# h-Remote.net
KiCad netlist of a schematic drawn in EAGLE
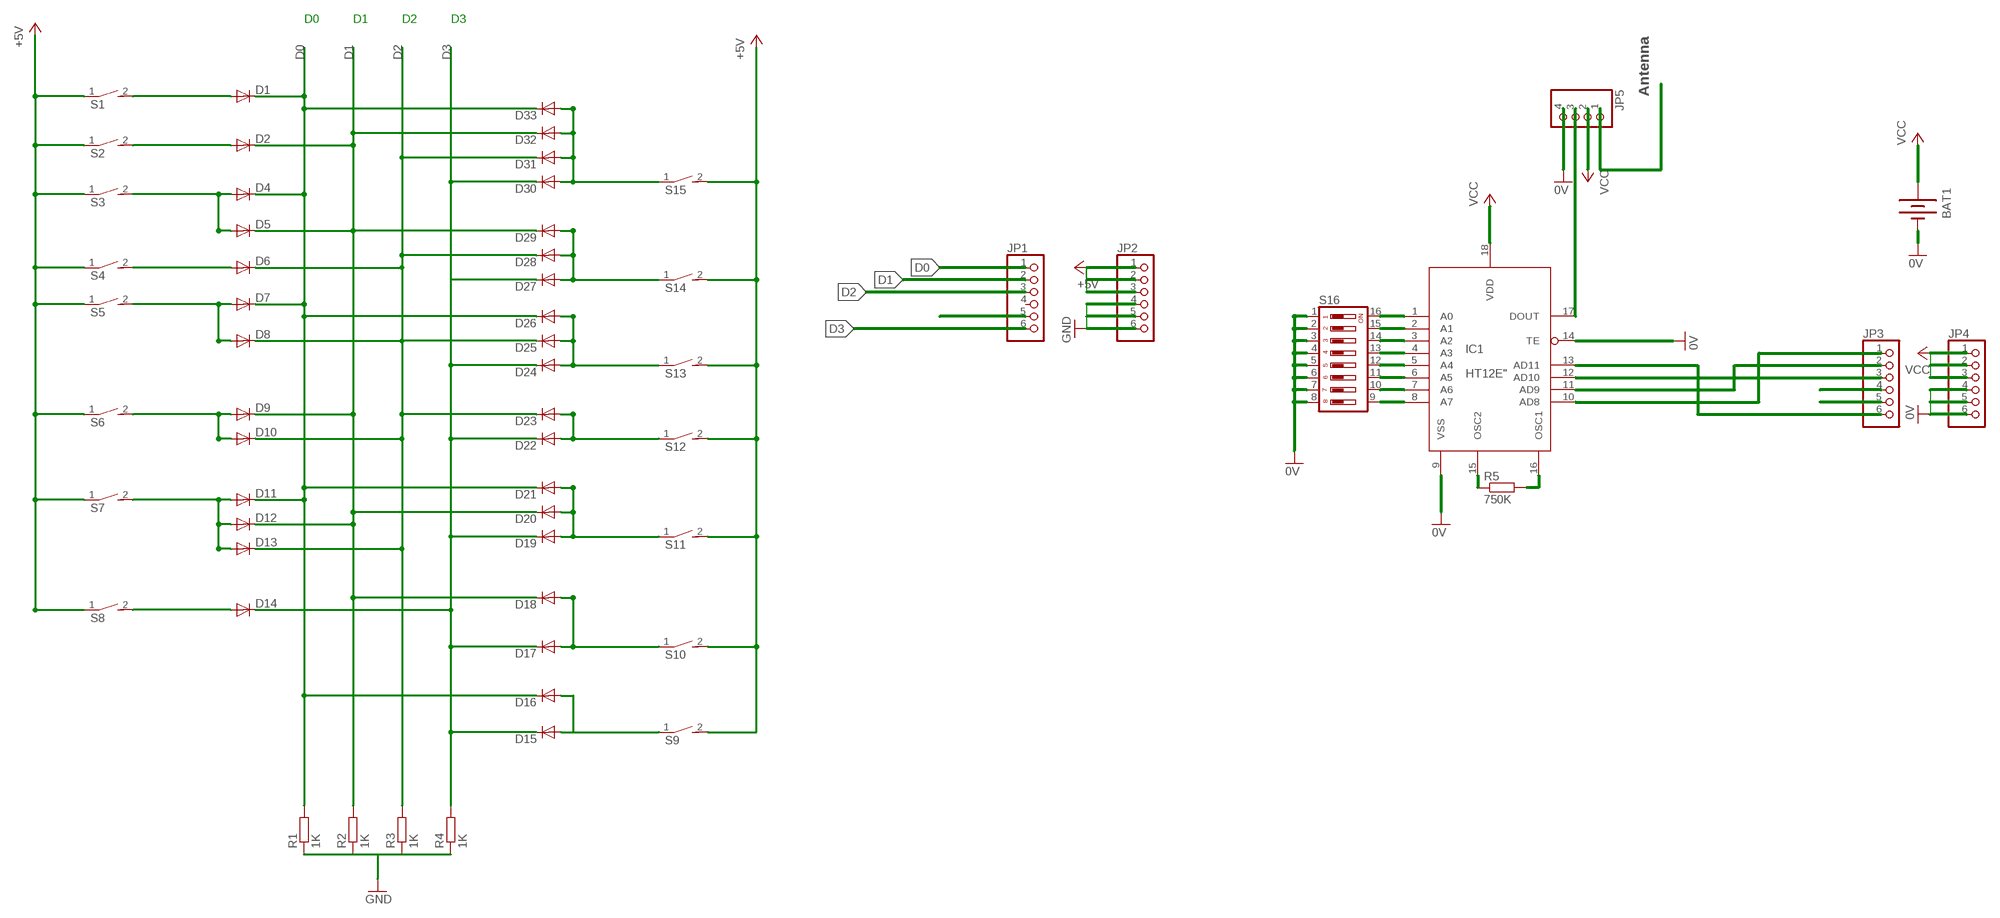
[diagram p0: schematic, sheet 1]

(export (version "E")
  (design (tool "Eeschema 10.0.6"))
  (components
    (comp (ref "BAT1")
      (value "BATTERY20PTH")
      (footprint "eagle-import:BATTCOM_20MM_PTH")
      (libsource (lib "eagle-import") (part "BATTERY20PTH"))
    )
    (comp (ref "D1")
      (value "DIODE-MELF-MLL41")
      (footprint "eagle-import:MELF-MLL41")
      (libsource (lib "eagle-import") (part "DIODE-MELF-MLL41"))
    )
    (comp (ref "D2")
      (value "DIODE-MELF-MLL41")
      (footprint "eagle-import:MELF-MLL41")
      (libsource (lib "eagle-import") (part "DIODE-MELF-MLL41"))
    )
    (comp (ref "D4")
      (value "DIODE-MELF-MLL41")
      (footprint "eagle-import:MELF-MLL41")
      (libsource (lib "eagle-import") (part "DIODE-MELF-MLL41"))
    )
    (comp (ref "D5")
      (value "DIODE-MELF-MLL41")
      (footprint "eagle-import:MELF-MLL41")
      (libsource (lib "eagle-import") (part "DIODE-MELF-MLL41"))
    )
    (comp (ref "D6")
      (value "DIODE-MELF-MLL41")
      (footprint "eagle-import:MELF-MLL41")
      (libsource (lib "eagle-import") (part "DIODE-MELF-MLL41"))
    )
    (comp (ref "D7")
      (value "DIODE-MELF-MLL41")
      (footprint "eagle-import:MELF-MLL41")
      (libsource (lib "eagle-import") (part "DIODE-MELF-MLL41"))
    )
    (comp (ref "D8")
      (value "DIODE-MELF-MLL41")
      (footprint "eagle-import:MELF-MLL41")
      (libsource (lib "eagle-import") (part "DIODE-MELF-MLL41"))
    )
    (comp (ref "D9")
      (value "DIODE-MELF-MLL41")
      (footprint "eagle-import:MELF-MLL41")
      (libsource (lib "eagle-import") (part "DIODE-MELF-MLL41"))
    )
    (comp (ref "D10")
      (value "DIODE-MELF-MLL41")
      (footprint "eagle-import:MELF-MLL41")
      (libsource (lib "eagle-import") (part "DIODE-MELF-MLL41"))
    )
    (comp (ref "D11")
      (value "DIODE-MELF-MLL41")
      (footprint "eagle-import:MELF-MLL41")
      (libsource (lib "eagle-import") (part "DIODE-MELF-MLL41"))
    )
    (comp (ref "D12")
      (value "DIODE-MELF-MLL41")
      (footprint "eagle-import:MELF-MLL41")
      (libsource (lib "eagle-import") (part "DIODE-MELF-MLL41"))
    )
    (comp (ref "D13")
      (value "DIODE-MELF-MLL41")
      (footprint "eagle-import:MELF-MLL41")
      (libsource (lib "eagle-import") (part "DIODE-MELF-MLL41"))
    )
    (comp (ref "D14")
      (value "DIODE-MELF-MLL41")
      (footprint "eagle-import:MELF-MLL41")
      (libsource (lib "eagle-import") (part "DIODE-MELF-MLL41"))
    )
    (comp (ref "D15")
      (value "DIODE-MELF-MLL41")
      (footprint "eagle-import:MELF-MLL41")
      (libsource (lib "eagle-import") (part "DIODE-MELF-MLL41"))
    )
    (comp (ref "D16")
      (value "DIODE-MELF-MLL41")
      (footprint "eagle-import:MELF-MLL41")
      (libsource (lib "eagle-import") (part "DIODE-MELF-MLL41"))
    )
    (comp (ref "D17")
      (value "DIODE-MELF-MLL41")
      (footprint "eagle-import:MELF-MLL41")
      (libsource (lib "eagle-import") (part "DIODE-MELF-MLL41"))
    )
    (comp (ref "D18")
      (value "DIODE-MELF-MLL41")
      (footprint "eagle-import:MELF-MLL41")
      (libsource (lib "eagle-import") (part "DIODE-MELF-MLL41"))
    )
    (comp (ref "D19")
      (value "DIODE-MELF-MLL41")
      (footprint "eagle-import:MELF-MLL41")
      (libsource (lib "eagle-import") (part "DIODE-MELF-MLL41"))
    )
    (comp (ref "D20")
      (value "DIODE-MELF-MLL41")
      (footprint "eagle-import:MELF-MLL41")
      (libsource (lib "eagle-import") (part "DIODE-MELF-MLL41"))
    )
    (comp (ref "D21")
      (value "DIODE-MELF-MLL41")
      (footprint "eagle-import:MELF-MLL41")
      (libsource (lib "eagle-import") (part "DIODE-MELF-MLL41"))
    )
    (comp (ref "D22")
      (value "DIODE-MELF-MLL41")
      (footprint "eagle-import:MELF-MLL41")
      (libsource (lib "eagle-import") (part "DIODE-MELF-MLL41"))
    )
    (comp (ref "D23")
      (value "DIODE-MELF-MLL41")
      (footprint "eagle-import:MELF-MLL41")
      (libsource (lib "eagle-import") (part "DIODE-MELF-MLL41"))
    )
    (comp (ref "D24")
      (value "DIODE-MELF-MLL41")
      (footprint "eagle-import:MELF-MLL41")
      (libsource (lib "eagle-import") (part "DIODE-MELF-MLL41"))
    )
    (comp (ref "D25")
      (value "DIODE-MELF-MLL41")
      (footprint "eagle-import:MELF-MLL41")
      (libsource (lib "eagle-import") (part "DIODE-MELF-MLL41"))
    )
    (comp (ref "D26")
      (value "DIODE-MELF-MLL41")
      (footprint "eagle-import:MELF-MLL41")
      (libsource (lib "eagle-import") (part "DIODE-MELF-MLL41"))
    )
    (comp (ref "D27")
      (value "DIODE-MELF-MLL41")
      (footprint "eagle-import:MELF-MLL41")
      (libsource (lib "eagle-import") (part "DIODE-MELF-MLL41"))
    )
    (comp (ref "D28")
      (value "DIODE-MELF-MLL41")
      (footprint "eagle-import:MELF-MLL41")
      (libsource (lib "eagle-import") (part "DIODE-MELF-MLL41"))
    )
    (comp (ref "D29")
      (value "DIODE-MELF-MLL41")
      (footprint "eagle-import:MELF-MLL41")
      (libsource (lib "eagle-import") (part "DIODE-MELF-MLL41"))
    )
    (comp (ref "D30")
      (value "DIODE-MELF-MLL41")
      (footprint "eagle-import:MELF-MLL41")
      (libsource (lib "eagle-import") (part "DIODE-MELF-MLL41"))
    )
    (comp (ref "D31")
      (value "DIODE-MELF-MLL41")
      (footprint "eagle-import:MELF-MLL41")
      (libsource (lib "eagle-import") (part "DIODE-MELF-MLL41"))
    )
    (comp (ref "D32")
      (value "DIODE-MELF-MLL41")
      (footprint "eagle-import:MELF-MLL41")
      (libsource (lib "eagle-import") (part "DIODE-MELF-MLL41"))
    )
    (comp (ref "D33")
      (value "DIODE-MELF-MLL41")
      (footprint "eagle-import:MELF-MLL41")
      (libsource (lib "eagle-import") (part "DIODE-MELF-MLL41"))
    )
    (comp (ref "IC1")
      (value "HT12E\"")
      (footprint "eagle-import:18-DIP-A")
      (libsource (lib "eagle-import") (part "HT12E{dblquote}"))
    )
    (comp (ref "JP1")
      (value "PINHD-1X6")
      (footprint "eagle-import:1X06")
      (libsource (lib "eagle-import") (part "PINHD-1X6"))
    )
    (comp (ref "JP2")
      (value "PINHD-1X6")
      (footprint "eagle-import:1X06")
      (libsource (lib "eagle-import") (part "PINHD-1X6"))
    )
    (comp (ref "JP3")
      (value "PINHD-1X6")
      (footprint "eagle-import:1X06")
      (libsource (lib "eagle-import") (part "PINHD-1X6"))
    )
    (comp (ref "JP4")
      (value "PINHD-1X6")
      (footprint "eagle-import:1X06")
      (libsource (lib "eagle-import") (part "PINHD-1X6"))
    )
    (comp (ref "JP5")
      (value "PINHD-1X4")
      (footprint "eagle-import:1X04")
      (libsource (lib "eagle-import") (part "PINHD-1X4"))
    )
    (comp (ref "R1")
      (value "1K")
      (footprint "eagle-import:R1206")
      (libsource (lib "eagle-import") (part "R-EU_R1206"))
    )
    (comp (ref "R2")
      (value "1K")
      (footprint "eagle-import:R1206")
      (libsource (lib "eagle-import") (part "R-EU_R1206"))
    )
    (comp (ref "R3")
      (value "1K")
      (footprint "eagle-import:R1206")
      (libsource (lib "eagle-import") (part "R-EU_R1206"))
    )
    (comp (ref "R4")
      (value "1K")
      (footprint "eagle-import:R1206")
      (libsource (lib "eagle-import") (part "R-EU_R1206"))
    )
    (comp (ref "R5")
      (value "750K")
      (footprint "eagle-import:0207_10")
      (libsource (lib "eagle-import") (part "R-EU_0207/10"))
    )
    (comp (ref "S1")
      (value "DS01E")
      (footprint "eagle-import:DS-01")
      (libsource (lib "eagle-import") (part "DS01E"))
    )
    (comp (ref "S2")
      (value "DS01E")
      (footprint "eagle-import:DS-01")
      (libsource (lib "eagle-import") (part "DS01E"))
    )
    (comp (ref "S3")
      (value "DS01E")
      (footprint "eagle-import:DS-01")
      (libsource (lib "eagle-import") (part "DS01E"))
    )
    (comp (ref "S4")
      (value "DS01E")
      (footprint "eagle-import:DS-01")
      (libsource (lib "eagle-import") (part "DS01E"))
    )
    (comp (ref "S5")
      (value "DS01E")
      (footprint "eagle-import:DS-01")
      (libsource (lib "eagle-import") (part "DS01E"))
    )
    (comp (ref "S6")
      (value "DS01E")
      (footprint "eagle-import:DS-01")
      (libsource (lib "eagle-import") (part "DS01E"))
    )
    (comp (ref "S7")
      (value "DS01E")
      (footprint "eagle-import:DS-01")
      (libsource (lib "eagle-import") (part "DS01E"))
    )
    (comp (ref "S8")
      (value "DS01E")
      (footprint "eagle-import:DS-01")
      (libsource (lib "eagle-import") (part "DS01E"))
    )
    (comp (ref "S9")
      (value "DS01E")
      (footprint "eagle-import:DS-01")
      (libsource (lib "eagle-import") (part "DS01E"))
    )
    (comp (ref "S10")
      (value "DS01E")
      (footprint "eagle-import:DS-01")
      (libsource (lib "eagle-import") (part "DS01E"))
    )
    (comp (ref "S11")
      (value "DS01E")
      (footprint "eagle-import:DS-01")
      (libsource (lib "eagle-import") (part "DS01E"))
    )
    (comp (ref "S12")
      (value "DS01E")
      (footprint "eagle-import:DS-01")
      (libsource (lib "eagle-import") (part "DS01E"))
    )
    (comp (ref "S13")
      (value "DS01E")
      (footprint "eagle-import:DS-01")
      (libsource (lib "eagle-import") (part "DS01E"))
    )
    (comp (ref "S14")
      (value "DS01E")
      (footprint "eagle-import:DS-01")
      (libsource (lib "eagle-import") (part "DS01E"))
    )
    (comp (ref "S15")
      (value "DS01E")
      (footprint "eagle-import:DS-01")
      (libsource (lib "eagle-import") (part "DS01E"))
    )
    (comp (ref "S16")
      (value "DIP08YL")
      (footprint "eagle-import:DIP08YL")
      (libsource (lib "eagle-import") (part "DIP08YL"))
    )
  )
  (nets
    (net (code "1") (name "+5V") (class "Default")
      (node (ref "JP2") (pin "1") (pinfunction "1_1") (pintype "passive"))
      (node (ref "JP2") (pin "2") (pinfunction "2_2") (pintype "passive"))
      (node (ref "JP2") (pin "3") (pinfunction "3_3") (pintype "passive"))
      (node (ref "S1") (pin "1") (pinfunction "1_1") (pintype "passive"))
      (node (ref "S10") (pin "2") (pinfunction "2_2") (pintype "passive"))
      (node (ref "S11") (pin "2") (pinfunction "2_2") (pintype "passive"))
      (node (ref "S12") (pin "2") (pinfunction "2_2") (pintype "passive"))
      (node (ref "S13") (pin "2") (pinfunction "2_2") (pintype "passive"))
      (node (ref "S14") (pin "2") (pinfunction "2_2") (pintype "passive"))
      (node (ref "S15") (pin "2") (pinfunction "2_2") (pintype "passive"))
      (node (ref "S2") (pin "1") (pinfunction "1_1") (pintype "passive"))
      (node (ref "S3") (pin "1") (pinfunction "1_1") (pintype "passive"))
      (node (ref "S4") (pin "1") (pinfunction "1_1") (pintype "passive"))
      (node (ref "S5") (pin "1") (pinfunction "1_1") (pintype "passive"))
      (node (ref "S6") (pin "1") (pinfunction "1_1") (pintype "passive"))
      (node (ref "S7") (pin "1") (pinfunction "1_1") (pintype "passive"))
      (node (ref "S8") (pin "1") (pinfunction "1_1") (pintype "passive"))
      (node (ref "S9") (pin "2") (pinfunction "2_2") (pintype "passive"))
    )
    (net (code "2") (name "0V") (class "Default")
      (node (ref "BAT1") (pin "2") (pinfunction "-_2") (pintype "power_in"))
      (node (ref "IC1") (pin "14") (pinfunction "TE_14") (pintype "power_in"))
      (node (ref "IC1") (pin "9") (pinfunction "VSS_9") (pintype "power_in"))
      (node (ref "JP4") (pin "4") (pinfunction "4_4") (pintype "passive"))
      (node (ref "JP4") (pin "5") (pinfunction "5_5") (pintype "passive"))
      (node (ref "JP4") (pin "6") (pinfunction "6_6") (pintype "passive"))
      (node (ref "JP5") (pin "4") (pinfunction "4_4") (pintype "passive"))
      (node (ref "S16") (pin "1") (pinfunction "1_1") (pintype "passive"))
      (node (ref "S16") (pin "2") (pinfunction "2_2") (pintype "passive"))
      (node (ref "S16") (pin "3") (pinfunction "3_3") (pintype "passive"))
      (node (ref "S16") (pin "4") (pinfunction "4_4") (pintype "passive"))
      (node (ref "S16") (pin "5") (pinfunction "5_5") (pintype "passive"))
      (node (ref "S16") (pin "6") (pinfunction "6_6") (pintype "passive"))
      (node (ref "S16") (pin "7") (pinfunction "7_7") (pintype "passive"))
      (node (ref "S16") (pin "8") (pinfunction "8_8") (pintype "passive"))
    )
    (net (code "3") (name "D0") (class "Default")
      (node (ref "D1") (pin "C") (pinfunction "C_C") (pintype "passive"))
      (node (ref "D11") (pin "C") (pinfunction "C_C") (pintype "passive"))
      (node (ref "D16") (pin "C") (pinfunction "C_C") (pintype "passive"))
      (node (ref "D21") (pin "C") (pinfunction "C_C") (pintype "passive"))
      (node (ref "D26") (pin "C") (pinfunction "C_C") (pintype "passive"))
      (node (ref "D33") (pin "C") (pinfunction "C_C") (pintype "passive"))
      (node (ref "D4") (pin "C") (pinfunction "C_C") (pintype "passive"))
      (node (ref "D7") (pin "C") (pinfunction "C_C") (pintype "passive"))
      (node (ref "JP1") (pin "1") (pinfunction "1_1") (pintype "passive"))
      (node (ref "R1") (pin "2") (pinfunction "2_2") (pintype "passive"))
    )
    (net (code "4") (name "D1") (class "Default")
      (node (ref "D12") (pin "C") (pinfunction "C_C") (pintype "passive"))
      (node (ref "D18") (pin "C") (pinfunction "C_C") (pintype "passive"))
      (node (ref "D2") (pin "C") (pinfunction "C_C") (pintype "passive"))
      (node (ref "D20") (pin "C") (pinfunction "C_C") (pintype "passive"))
      (node (ref "D29") (pin "C") (pinfunction "C_C") (pintype "passive"))
      (node (ref "D32") (pin "C") (pinfunction "C_C") (pintype "passive"))
      (node (ref "D5") (pin "C") (pinfunction "C_C") (pintype "passive"))
      (node (ref "D9") (pin "C") (pinfunction "C_C") (pintype "passive"))
      (node (ref "JP1") (pin "2") (pinfunction "2_2") (pintype "passive"))
      (node (ref "R2") (pin "2") (pinfunction "2_2") (pintype "passive"))
    )
    (net (code "5") (name "D2") (class "Default")
      (node (ref "D10") (pin "C") (pinfunction "C_C") (pintype "passive"))
      (node (ref "D13") (pin "C") (pinfunction "C_C") (pintype "passive"))
      (node (ref "D23") (pin "C") (pinfunction "C_C") (pintype "passive"))
      (node (ref "D25") (pin "C") (pinfunction "C_C") (pintype "passive"))
      (node (ref "D28") (pin "C") (pinfunction "C_C") (pintype "passive"))
      (node (ref "D31") (pin "C") (pinfunction "C_C") (pintype "passive"))
      (node (ref "D6") (pin "C") (pinfunction "C_C") (pintype "passive"))
      (node (ref "D8") (pin "C") (pinfunction "C_C") (pintype "passive"))
      (node (ref "JP1") (pin "3") (pinfunction "3_3") (pintype "passive"))
      (node (ref "R3") (pin "2") (pinfunction "2_2") (pintype "passive"))
    )
    (net (code "6") (name "D3") (class "Default")
      (node (ref "D14") (pin "C") (pinfunction "C_C") (pintype "passive"))
      (node (ref "D15") (pin "C") (pinfunction "C_C") (pintype "passive"))
      (node (ref "D17") (pin "C") (pinfunction "C_C") (pintype "passive"))
      (node (ref "D19") (pin "C") (pinfunction "C_C") (pintype "passive"))
      (node (ref "D22") (pin "C") (pinfunction "C_C") (pintype "passive"))
      (node (ref "D24") (pin "C") (pinfunction "C_C") (pintype "passive"))
      (node (ref "D27") (pin "C") (pinfunction "C_C") (pintype "passive"))
      (node (ref "D30") (pin "C") (pinfunction "C_C") (pintype "passive"))
      (node (ref "JP1") (pin "6") (pinfunction "6_6") (pintype "passive"))
      (node (ref "R4") (pin "2") (pinfunction "2_2") (pintype "passive"))
    )
    (net (code "7") (name "GND") (class "Default")
      (node (ref "JP2") (pin "4") (pinfunction "4_4") (pintype "passive"))
      (node (ref "JP2") (pin "5") (pinfunction "5_5") (pintype "passive"))
      (node (ref "JP2") (pin "6") (pinfunction "6_6") (pintype "passive"))
      (node (ref "R1") (pin "1") (pinfunction "1_1") (pintype "passive"))
      (node (ref "R2") (pin "1") (pinfunction "1_1") (pintype "passive"))
      (node (ref "R3") (pin "1") (pinfunction "1_1") (pintype "passive"))
      (node (ref "R4") (pin "1") (pinfunction "1_1") (pintype "passive"))
    )
    (net (code "8") (name "Net-(D1-PadA)") (class "Default")
      (node (ref "D1") (pin "A") (pinfunction "A_A") (pintype "passive"))
      (node (ref "S1") (pin "2") (pinfunction "2_2") (pintype "passive"))
    )
    (net (code "9") (name "Net-(D2-PadA)") (class "Default")
      (node (ref "D2") (pin "A") (pinfunction "A_A") (pintype "passive"))
      (node (ref "S2") (pin "2") (pinfunction "2_2") (pintype "passive"))
    )
    (net (code "10") (name "Net-(D4-PadA)") (class "Default")
      (node (ref "D4") (pin "A") (pinfunction "A_A") (pintype "passive"))
      (node (ref "D5") (pin "A") (pinfunction "A_A") (pintype "passive"))
      (node (ref "S3") (pin "2") (pinfunction "2_2") (pintype "passive"))
    )
    (net (code "11") (name "Net-(D6-PadA)") (class "Default")
      (node (ref "D6") (pin "A") (pinfunction "A_A") (pintype "passive"))
      (node (ref "S4") (pin "2") (pinfunction "2_2") (pintype "passive"))
    )
    (net (code "12") (name "Net-(D7-PadA)") (class "Default")
      (node (ref "D7") (pin "A") (pinfunction "A_A") (pintype "passive"))
      (node (ref "D8") (pin "A") (pinfunction "A_A") (pintype "passive"))
      (node (ref "S5") (pin "2") (pinfunction "2_2") (pintype "passive"))
    )
    (net (code "13") (name "Net-(D10-PadA)") (class "Default")
      (node (ref "D10") (pin "A") (pinfunction "A_A") (pintype "passive"))
      (node (ref "D9") (pin "A") (pinfunction "A_A") (pintype "passive"))
      (node (ref "S6") (pin "2") (pinfunction "2_2") (pintype "passive"))
    )
    (net (code "14") (name "Net-(D11-PadA)") (class "Default")
      (node (ref "D11") (pin "A") (pinfunction "A_A") (pintype "passive"))
      (node (ref "D12") (pin "A") (pinfunction "A_A") (pintype "passive"))
      (node (ref "D13") (pin "A") (pinfunction "A_A") (pintype "passive"))
      (node (ref "S7") (pin "2") (pinfunction "2_2") (pintype "passive"))
    )
    (net (code "15") (name "Net-(D14-PadA)") (class "Default")
      (node (ref "D14") (pin "A") (pinfunction "A_A") (pintype "passive"))
      (node (ref "S8") (pin "2") (pinfunction "2_2") (pintype "passive"))
    )
    (net (code "16") (name "Net-(D15-PadA)") (class "Default")
      (node (ref "D15") (pin "A") (pinfunction "A_A") (pintype "passive"))
      (node (ref "D16") (pin "A") (pinfunction "A_A") (pintype "passive"))
      (node (ref "S9") (pin "1") (pinfunction "1_1") (pintype "passive"))
    )
    (net (code "17") (name "Net-(D17-PadA)") (class "Default")
      (node (ref "D17") (pin "A") (pinfunction "A_A") (pintype "passive"))
      (node (ref "D18") (pin "A") (pinfunction "A_A") (pintype "passive"))
      (node (ref "S10") (pin "1") (pinfunction "1_1") (pintype "passive"))
    )
    (net (code "18") (name "Net-(D19-PadA)") (class "Default")
      (node (ref "D19") (pin "A") (pinfunction "A_A") (pintype "passive"))
      (node (ref "D20") (pin "A") (pinfunction "A_A") (pintype "passive"))
      (node (ref "D21") (pin "A") (pinfunction "A_A") (pintype "passive"))
      (node (ref "S11") (pin "1") (pinfunction "1_1") (pintype "passive"))
    )
    (net (code "19") (name "Net-(D22-PadA)") (class "Default")
      (node (ref "D22") (pin "A") (pinfunction "A_A") (pintype "passive"))
      (node (ref "D23") (pin "A") (pinfunction "A_A") (pintype "passive"))
      (node (ref "S12") (pin "1") (pinfunction "1_1") (pintype "passive"))
    )
    (net (code "20") (name "Net-(D24-PadA)") (class "Default")
      (node (ref "D24") (pin "A") (pinfunction "A_A") (pintype "passive"))
      (node (ref "D25") (pin "A") (pinfunction "A_A") (pintype "passive"))
      (node (ref "D26") (pin "A") (pinfunction "A_A") (pintype "passive"))
      (node (ref "S13") (pin "1") (pinfunction "1_1") (pintype "passive"))
    )
    (net (code "21") (name "Net-(D27-PadA)") (class "Default")
      (node (ref "D27") (pin "A") (pinfunction "A_A") (pintype "passive"))
      (node (ref "D28") (pin "A") (pinfunction "A_A") (pintype "passive"))
      (node (ref "D29") (pin "A") (pinfunction "A_A") (pintype "passive"))
      (node (ref "S14") (pin "1") (pinfunction "1_1") (pintype "passive"))
    )
    (net (code "22") (name "Net-(D30-PadA)") (class "Default")
      (node (ref "D30") (pin "A") (pinfunction "A_A") (pintype "passive"))
      (node (ref "D31") (pin "A") (pinfunction "A_A") (pintype "passive"))
      (node (ref "D32") (pin "A") (pinfunction "A_A") (pintype "passive"))
      (node (ref "D33") (pin "A") (pinfunction "A_A") (pintype "passive"))
      (node (ref "S15") (pin "1") (pinfunction "1_1") (pintype "passive"))
    )
    (net (code "23") (name "Net-(IC1-A0)") (class "Default")
      (node (ref "IC1") (pin "1") (pinfunction "A0_1") (pintype "input"))
      (node (ref "S16") (pin "16") (pinfunction "16_16") (pintype "passive"))
    )
    (net (code "24") (name "Net-(IC1-A1)") (class "Default")
      (node (ref "IC1") (pin "2") (pinfunction "A1_2") (pintype "input"))
      (node (ref "S16") (pin "15") (pinfunction "15_15") (pintype "passive"))
    )
    (net (code "25") (name "Net-(IC1-A2)") (class "Default")
      (node (ref "IC1") (pin "3") (pinfunction "A2_3") (pintype "input"))
      (node (ref "S16") (pin "14") (pinfunction "14_14") (pintype "passive"))
    )
    (net (code "26") (name "Net-(IC1-A3)") (class "Default")
      (node (ref "IC1") (pin "4") (pinfunction "A3_4") (pintype "input"))
      (node (ref "S16") (pin "13") (pinfunction "13_13") (pintype "passive"))
    )
    (net (code "27") (name "Net-(IC1-A4)") (class "Default")
      (node (ref "IC1") (pin "5") (pinfunction "A4_5") (pintype "input"))
      (node (ref "S16") (pin "12") (pinfunction "12_12") (pintype "passive"))
    )
    (net (code "28") (name "Net-(IC1-A5)") (class "Default")
      (node (ref "IC1") (pin "6") (pinfunction "A5_6") (pintype "input"))
      (node (ref "S16") (pin "11") (pinfunction "11_11") (pintype "passive"))
    )
    (net (code "29") (name "Net-(IC1-A6)") (class "Default")
      (node (ref "IC1") (pin "7") (pinfunction "A6_7") (pintype "input"))
      (node (ref "S16") (pin "10") (pinfunction "10_10") (pintype "passive"))
    )
    (net (code "30") (name "Net-(IC1-A7)") (class "Default")
      (node (ref "IC1") (pin "8") (pinfunction "A7_8") (pintype "input"))
      (node (ref "S16") (pin "9") (pinfunction "9_9") (pintype "passive"))
    )
    (net (code "31") (name "Net-(IC1-AD8)") (class "Default")
      (node (ref "IC1") (pin "10") (pinfunction "AD8_10") (pintype "input"))
      (node (ref "JP3") (pin "1") (pinfunction "1_1") (pintype "passive"))
    )
    (net (code "32") (name "Net-(IC1-AD9)") (class "Default")
      (node (ref "IC1") (pin "11") (pinfunction "AD9_11") (pintype "input"))
      (node (ref "JP3") (pin "2") (pinfunction "2_2") (pintype "passive"))
    )
    (net (code "33") (name "Net-(IC1-AD10)") (class "Default")
      (node (ref "IC1") (pin "12") (pinfunction "AD10_12") (pintype "input"))
      (node (ref "JP3") (pin "3") (pinfunction "3_3") (pintype "passive"))
    )
    (net (code "34") (name "Net-(IC1-AD11)") (class "Default")
      (node (ref "IC1") (pin "13") (pinfunction "AD11_13") (pintype "input"))
      (node (ref "JP3") (pin "6") (pinfunction "6_6") (pintype "passive"))
    )
    (net (code "35") (name "Net-(IC1-DOUT)") (class "Default")
      (node (ref "IC1") (pin "17") (pinfunction "DOUT_17") (pintype "output"))
      (node (ref "JP5") (pin "3") (pinfunction "3_3") (pintype "passive"))
    )
    (net (code "36") (name "Net-(IC1-OSC1)") (class "Default")
      (node (ref "IC1") (pin "16") (pinfunction "OSC1_16") (pintype "input"))
      (node (ref "R5") (pin "2") (pinfunction "2_2") (pintype "passive"))
    )
    (net (code "37") (name "Net-(IC1-OSC2)") (class "Default")
      (node (ref "IC1") (pin "15") (pinfunction "OSC2_15") (pintype "input"))
      (node (ref "R5") (pin "1") (pinfunction "1_1") (pintype "passive"))
    )
    (net (code "38") (name "VCC") (class "Default")
      (node (ref "BAT1") (pin "1") (pinfunction "+_1") (pintype "power_in"))
      (node (ref "IC1") (pin "18") (pinfunction "VDD_18") (pintype "power_in"))
      (node (ref "JP4") (pin "1") (pinfunction "1_1") (pintype "passive"))
      (node (ref "JP4") (pin "2") (pinfunction "2_2") (pintype "passive"))
      (node (ref "JP4") (pin "3") (pinfunction "3_3") (pintype "passive"))
      (node (ref "JP5") (pin "2") (pinfunction "2_2") (pintype "passive"))
    )
    (net (code "39") (name "unconnected-(JP1-Pad4)") (class "Default")
      (node (ref "JP1") (pin "4") (pinfunction "4_4") (pintype "passive"))
    )
    (net (code "40") (name "unconnected-(JP1-Pad5)") (class "Default")
      (node (ref "JP1") (pin "5") (pinfunction "5_5") (pintype "passive"))
    )
    (net (code "41") (name "unconnected-(JP3-Pad4)") (class "Default")
      (node (ref "JP3") (pin "4") (pinfunction "4_4") (pintype "passive"))
    )
    (net (code "42") (name "unconnected-(JP3-Pad5)") (class "Default")
      (node (ref "JP3") (pin "5") (pinfunction "5_5") (pintype "passive"))
    )
    (net (code "43") (name "unconnected-(JP5-Pad1)") (class "Default")
      (node (ref "JP5") (pin "1") (pinfunction "1_1") (pintype "passive"))
    )
  )
)
